# ProDocument_20LEDBarGraph_2024-07-22.net
KiCad netlist of a schematic drawn in EasyEDA Pro
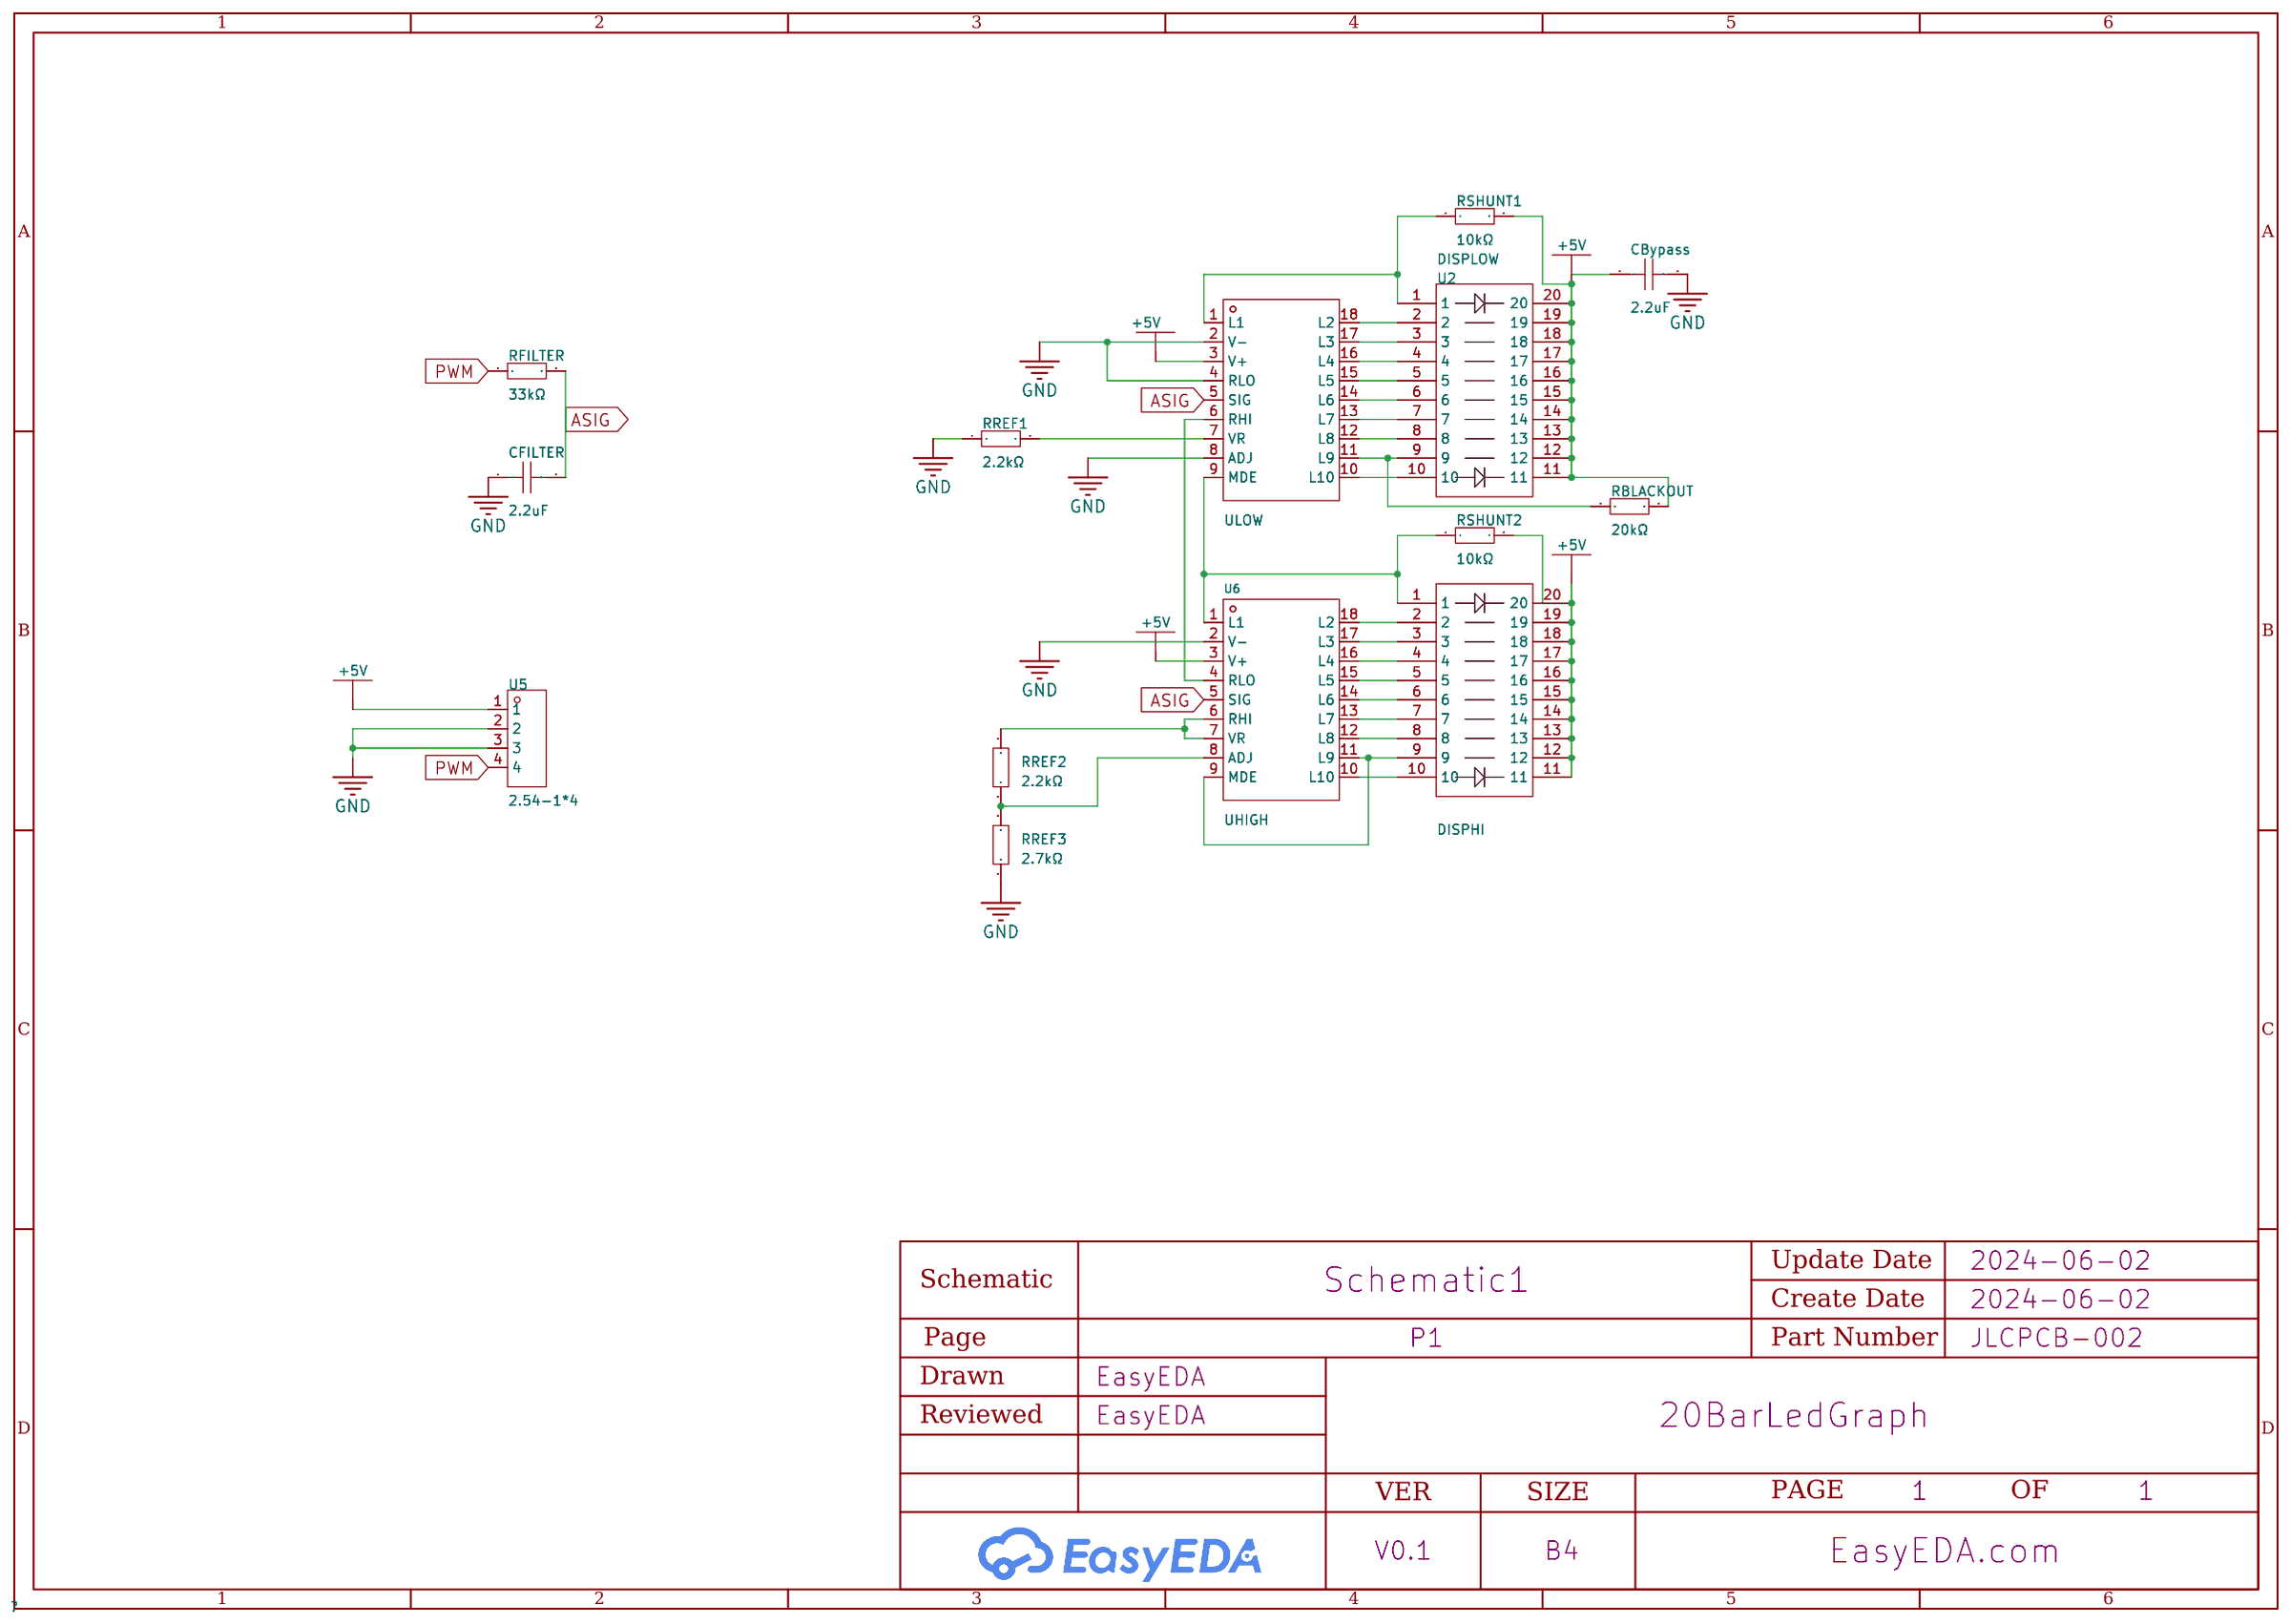
[diagram p0: schematic sheet]

(export (version "E")
  (design (tool "Eeschema 10.0.6"))
  (components
    (comp (ref "CBypass")
      (value "2.2uF")
      (footprint "easyedapro:CAP-TH_L6.0-W3.8-P5.08-D0.6")
      (fields
        (field (name "Manufacturer Part") "CD1H225KC9BER1F100")
        (field (name "Manufacturer") "Dersonic(德尔创)")
      )
      (libsource (lib "easyedapro") (part "CD1H225KC9BER1F100"))
    )
    (comp (ref "CFILTER")
      (value "2.2uF")
      (footprint "easyedapro:CAP-TH_L6.0-W3.8-P5.08-D0.6")
      (fields
        (field (name "Manufacturer Part") "CD1H225KC9BER1F100")
        (field (name "Manufacturer") "Dersonic(德尔创)")
      )
      (libsource (lib "easyedapro") (part "CD1H225KC9BER1F100"))
    )
    (comp (ref "RBLACKOUT")
      (value "20kΩ")
      (footprint "easyedapro:R0805")
      (fields (field (name "Manufacturer Part") "RC0805JR-0733KL") (field (name "Manufacturer") "YAGEO(国巨)"))
      (libsource (lib "easyedapro") (part "RC0805JR-0733KL"))
    )
    (comp (ref "RFILTER")
      (value "33kΩ")
      (footprint "easyedapro:R0805")
      (fields (field (name "Manufacturer Part") "RC0805JR-0733KL") (field (name "Manufacturer") "YAGEO(国巨)"))
      (libsource (lib "easyedapro") (part "RC0805JR-0733KL"))
    )
    (comp (ref "RREF1")
      (value "2.2kΩ")
      (footprint "easyedapro:R0805")
      (fields (field (name "Manufacturer Part") "RC0805JR-0733KL") (field (name "Manufacturer") "YAGEO(国巨)"))
      (libsource (lib "easyedapro") (part "RC0805JR-0733KL"))
    )
    (comp (ref "RREF2")
      (value "2.2kΩ")
      (footprint "easyedapro:R0805")
      (fields (field (name "Manufacturer Part") "RC0805JR-0733KL") (field (name "Manufacturer") "YAGEO(国巨)"))
      (libsource (lib "easyedapro") (part "RC0805JR-0733KL"))
    )
    (comp (ref "RREF3")
      (value "2.7kΩ")
      (footprint "easyedapro:R0805")
      (fields (field (name "Manufacturer Part") "RC0805JR-0733KL") (field (name "Manufacturer") "YAGEO(国巨)"))
      (libsource (lib "easyedapro") (part "RC0805JR-0733KL"))
    )
    (comp (ref "RSHUNT1")
      (value "10kΩ")
      (footprint "easyedapro:R0805")
      (fields (field (name "Manufacturer Part") "RC0805JR-0733KL") (field (name "Manufacturer") "YAGEO(国巨)"))
      (libsource (lib "easyedapro") (part "RC0805JR-0733KL"))
    )
    (comp (ref "RSHUNT2")
      (value "10kΩ")
      (footprint "easyedapro:R0805")
      (fields (field (name "Manufacturer Part") "RC0805JR-0733KL") (field (name "Manufacturer") "YAGEO(国巨)"))
      (libsource (lib "easyedapro") (part "RC0805JR-0733KL"))
    )
    (comp (ref "U1")
      (value "ULOW")
      (footprint "easyedapro:DIP-18_L23.0-W6.5-P2.54-LS7.6-BL")
      (fields (field (name "Manufacturer Part") "LM3914N-1/NOPB") (field (name "Manufacturer") "TI(德州仪器)"))
      (libsource (lib "easyedapro") (part "LM3914N-1/NOPB"))
    )
    (comp (ref "U2")
      (value "DISPLOW")
      (footprint "easyedapro:DC-10GWA")
      (libsource (lib "easyedapro") (part "DC-10GWA"))
    )
    (comp (ref "U3")
      (value "DISPHI")
      (footprint "easyedapro:DC-10GWA")
      (libsource (lib "easyedapro") (part "DC-10GWA"))
    )
    (comp (ref "U5")
      (value "2.54-1*4")
      (footprint "easyedapro:HDR-TH_4P-P2.54-V-M-1")
      (description "Pin Structure:1x4P Pitch:2.54mm Number of Rows:Plugin Number of Pins:4P")
      (fields (field (name "Manufacturer") "ZHOURI(洲日)"))
      (libsource (lib "easyedapro") (part "2.54-1*4"))
    )
    (comp (ref "U6")
      (value "UHIGH")
      (footprint "easyedapro:DIP-18_L23.0-W6.5-P2.54-LS7.6-BL")
      (fields (field (name "Manufacturer Part") "LM3914N-1/NOPB") (field (name "Manufacturer") "TI(德州仪器)"))
      (libsource (lib "easyedapro") (part "LM3914N-1/NOPB"))
    )
  )
  (nets
    (net (code "1") (name "+5V") (class "Default")
      (node (ref "CBypass") (pin "1") (pinfunction "1_1") (pintype "unspecified"))
      (node (ref "RBLACKOUT") (pin "2") (pinfunction "2_2") (pintype "input"))
      (node (ref "RSHUNT1") (pin "2") (pinfunction "2_2") (pintype "input"))
      (node (ref "RSHUNT2") (pin "2") (pinfunction "2_2") (pintype "input"))
      (node (ref "U1") (pin "3") (pinfunction "V+_3") (pintype "input"))
      (node (ref "U2") (pin "11") (pinfunction "11_11") (pintype "input"))
      (node (ref "U2") (pin "12") (pinfunction "12_12") (pintype "input"))
      (node (ref "U2") (pin "13") (pinfunction "13_13") (pintype "input"))
      (node (ref "U2") (pin "14") (pinfunction "14_14") (pintype "input"))
      (node (ref "U2") (pin "15") (pinfunction "15_15") (pintype "input"))
      (node (ref "U2") (pin "16") (pinfunction "16_16") (pintype "input"))
      (node (ref "U2") (pin "17") (pinfunction "17_17") (pintype "input"))
      (node (ref "U2") (pin "18") (pinfunction "18_18") (pintype "input"))
      (node (ref "U2") (pin "19") (pinfunction "19_19") (pintype "input"))
      (node (ref "U2") (pin "20") (pinfunction "20_20") (pintype "input"))
      (node (ref "U3") (pin "11") (pinfunction "11_11") (pintype "input"))
      (node (ref "U3") (pin "12") (pinfunction "12_12") (pintype "input"))
      (node (ref "U3") (pin "13") (pinfunction "13_13") (pintype "input"))
      (node (ref "U3") (pin "14") (pinfunction "14_14") (pintype "input"))
      (node (ref "U3") (pin "15") (pinfunction "15_15") (pintype "input"))
      (node (ref "U3") (pin "16") (pinfunction "16_16") (pintype "input"))
      (node (ref "U3") (pin "17") (pinfunction "17_17") (pintype "input"))
      (node (ref "U3") (pin "18") (pinfunction "18_18") (pintype "input"))
      (node (ref "U3") (pin "19") (pinfunction "19_19") (pintype "input"))
      (node (ref "U3") (pin "20") (pinfunction "20_20") (pintype "input"))
      (node (ref "U5") (pin "1") (pinfunction "1_1") (pintype "unspecified"))
      (node (ref "U6") (pin "3") (pinfunction "V+_3") (pintype "input"))
    )
    (net (code "2") (name "ASIG") (class "Default")
      (node (ref "CFILTER") (pin "2") (pinfunction "2_2") (pintype "unspecified"))
      (node (ref "RFILTER") (pin "2") (pinfunction "2_2") (pintype "input"))
      (node (ref "U1") (pin "5") (pinfunction "SIG_5") (pintype "input"))
      (node (ref "U6") (pin "5") (pinfunction "SIG_5") (pintype "input"))
    )
    (net (code "3") (name "GND") (class "Default")
      (node (ref "CBypass") (pin "2") (pinfunction "2_2") (pintype "unspecified"))
      (node (ref "CFILTER") (pin "1") (pinfunction "1_1") (pintype "unspecified"))
      (node (ref "RREF1") (pin "1") (pinfunction "1_1") (pintype "input"))
      (node (ref "RREF3") (pin "1") (pinfunction "1_1") (pintype "input"))
      (node (ref "U1") (pin "2") (pinfunction "V-_2") (pintype "input"))
      (node (ref "U1") (pin "4") (pinfunction "RLO_4") (pintype "input"))
      (node (ref "U1") (pin "8") (pinfunction "ADJ_8") (pintype "input"))
      (node (ref "U5") (pin "2") (pinfunction "2_2") (pintype "unspecified"))
      (node (ref "U5") (pin "3") (pinfunction "3_3") (pintype "unspecified"))
      (node (ref "U6") (pin "2") (pinfunction "V-_2") (pintype "input"))
    )
    (net (code "4") (name "Net-(U1-L1)") (class "Default")
      (node (ref "RSHUNT1") (pin "1") (pinfunction "1_1") (pintype "input"))
      (node (ref "U1") (pin "1") (pinfunction "L1_1") (pintype "input"))
      (node (ref "U2") (pin "1") (pinfunction "1_1") (pintype "input"))
    )
    (net (code "5") (name "Net-(U1-L2)") (class "Default")
      (node (ref "U1") (pin "18") (pinfunction "L2_18") (pintype "input"))
      (node (ref "U2") (pin "2") (pinfunction "2_2") (pintype "input"))
    )
    (net (code "6") (name "Net-(U1-L3)") (class "Default")
      (node (ref "U1") (pin "17") (pinfunction "L3_17") (pintype "input"))
      (node (ref "U2") (pin "3") (pinfunction "3_3") (pintype "input"))
    )
    (net (code "7") (name "Net-(U1-L4)") (class "Default")
      (node (ref "U1") (pin "16") (pinfunction "L4_16") (pintype "input"))
      (node (ref "U2") (pin "4") (pinfunction "4_4") (pintype "input"))
    )
    (net (code "8") (name "Net-(U1-L5)") (class "Default")
      (node (ref "U1") (pin "15") (pinfunction "L5_15") (pintype "input"))
      (node (ref "U2") (pin "5") (pinfunction "5_5") (pintype "input"))
    )
    (net (code "9") (name "Net-(U1-L6)") (class "Default")
      (node (ref "U1") (pin "14") (pinfunction "L6_14") (pintype "input"))
      (node (ref "U2") (pin "6") (pinfunction "6_6") (pintype "input"))
    )
    (net (code "10") (name "Net-(U1-L7)") (class "Default")
      (node (ref "U1") (pin "13") (pinfunction "L7_13") (pintype "input"))
      (node (ref "U2") (pin "7") (pinfunction "7_7") (pintype "input"))
    )
    (net (code "11") (name "Net-(U1-L8)") (class "Default")
      (node (ref "U1") (pin "12") (pinfunction "L8_12") (pintype "input"))
      (node (ref "U2") (pin "8") (pinfunction "8_8") (pintype "input"))
    )
    (net (code "12") (name "Net-(U1-L9)") (class "Default")
      (node (ref "RBLACKOUT") (pin "1") (pinfunction "1_1") (pintype "input"))
      (node (ref "U1") (pin "11") (pinfunction "L9_11") (pintype "input"))
      (node (ref "U2") (pin "9") (pinfunction "9_9") (pintype "input"))
    )
    (net (code "13") (name "Net-(U1-L10)") (class "Default")
      (node (ref "U1") (pin "10") (pinfunction "L10_10") (pintype "input"))
      (node (ref "U2") (pin "10") (pinfunction "10_10") (pintype "input"))
    )
    (net (code "14") (name "Net-(U1-MDE)") (class "Default")
      (node (ref "RSHUNT2") (pin "1") (pinfunction "1_1") (pintype "input"))
      (node (ref "U1") (pin "9") (pinfunction "MDE_9") (pintype "input"))
      (node (ref "U3") (pin "1") (pinfunction "1_1") (pintype "input"))
      (node (ref "U6") (pin "1") (pinfunction "L1_1") (pintype "input"))
    )
    (net (code "15") (name "Net-(U1-RHI)") (class "Default")
      (node (ref "U1") (pin "6") (pinfunction "RHI_6") (pintype "input"))
      (node (ref "U6") (pin "4") (pinfunction "RLO_4") (pintype "input"))
    )
    (net (code "16") (name "Net-(U1-VR)") (class "Default")
      (node (ref "RREF1") (pin "2") (pinfunction "2_2") (pintype "input"))
      (node (ref "U1") (pin "7") (pinfunction "VR_7") (pintype "input"))
    )
    (net (code "17") (name "Net-(U6-ADJ)") (class "Default")
      (node (ref "RREF2") (pin "1") (pinfunction "1_1") (pintype "input"))
      (node (ref "RREF3") (pin "2") (pinfunction "2_2") (pintype "input"))
      (node (ref "U6") (pin "8") (pinfunction "ADJ_8") (pintype "input"))
    )
    (net (code "18") (name "Net-(U6-L2)") (class "Default")
      (node (ref "U3") (pin "2") (pinfunction "2_2") (pintype "input"))
      (node (ref "U6") (pin "18") (pinfunction "L2_18") (pintype "input"))
    )
    (net (code "19") (name "Net-(U6-L3)") (class "Default")
      (node (ref "U3") (pin "3") (pinfunction "3_3") (pintype "input"))
      (node (ref "U6") (pin "17") (pinfunction "L3_17") (pintype "input"))
    )
    (net (code "20") (name "Net-(U6-L4)") (class "Default")
      (node (ref "U3") (pin "4") (pinfunction "4_4") (pintype "input"))
      (node (ref "U6") (pin "16") (pinfunction "L4_16") (pintype "input"))
    )
    (net (code "21") (name "Net-(U6-L5)") (class "Default")
      (node (ref "U3") (pin "5") (pinfunction "5_5") (pintype "input"))
      (node (ref "U6") (pin "15") (pinfunction "L5_15") (pintype "input"))
    )
    (net (code "22") (name "Net-(U6-L6)") (class "Default")
      (node (ref "U3") (pin "6") (pinfunction "6_6") (pintype "input"))
      (node (ref "U6") (pin "14") (pinfunction "L6_14") (pintype "input"))
    )
    (net (code "23") (name "Net-(U6-L7)") (class "Default")
      (node (ref "U3") (pin "7") (pinfunction "7_7") (pintype "input"))
      (node (ref "U6") (pin "13") (pinfunction "L7_13") (pintype "input"))
    )
    (net (code "24") (name "Net-(U6-L8)") (class "Default")
      (node (ref "U3") (pin "8") (pinfunction "8_8") (pintype "input"))
      (node (ref "U6") (pin "12") (pinfunction "L8_12") (pintype "input"))
    )
    (net (code "25") (name "Net-(U6-L9)") (class "Default")
      (node (ref "U3") (pin "9") (pinfunction "9_9") (pintype "input"))
      (node (ref "U6") (pin "11") (pinfunction "L9_11") (pintype "input"))
      (node (ref "U6") (pin "9") (pinfunction "MDE_9") (pintype "input"))
    )
    (net (code "26") (name "Net-(U6-L10)") (class "Default")
      (node (ref "U3") (pin "10") (pinfunction "10_10") (pintype "input"))
      (node (ref "U6") (pin "10") (pinfunction "L10_10") (pintype "input"))
    )
    (net (code "27") (name "Net-(U6-RHI)") (class "Default")
      (node (ref "RREF2") (pin "2") (pinfunction "2_2") (pintype "input"))
      (node (ref "U6") (pin "6") (pinfunction "RHI_6") (pintype "input"))
      (node (ref "U6") (pin "7") (pinfunction "VR_7") (pintype "input"))
    )
    (net (code "28") (name "PWM") (class "Default")
      (node (ref "RFILTER") (pin "1") (pinfunction "1_1") (pintype "input"))
      (node (ref "U5") (pin "4") (pinfunction "4_4") (pintype "unspecified"))
    )
  )
)
